# RFID_Shield.net
KiCad netlist of a schematic drawn in EAGLE
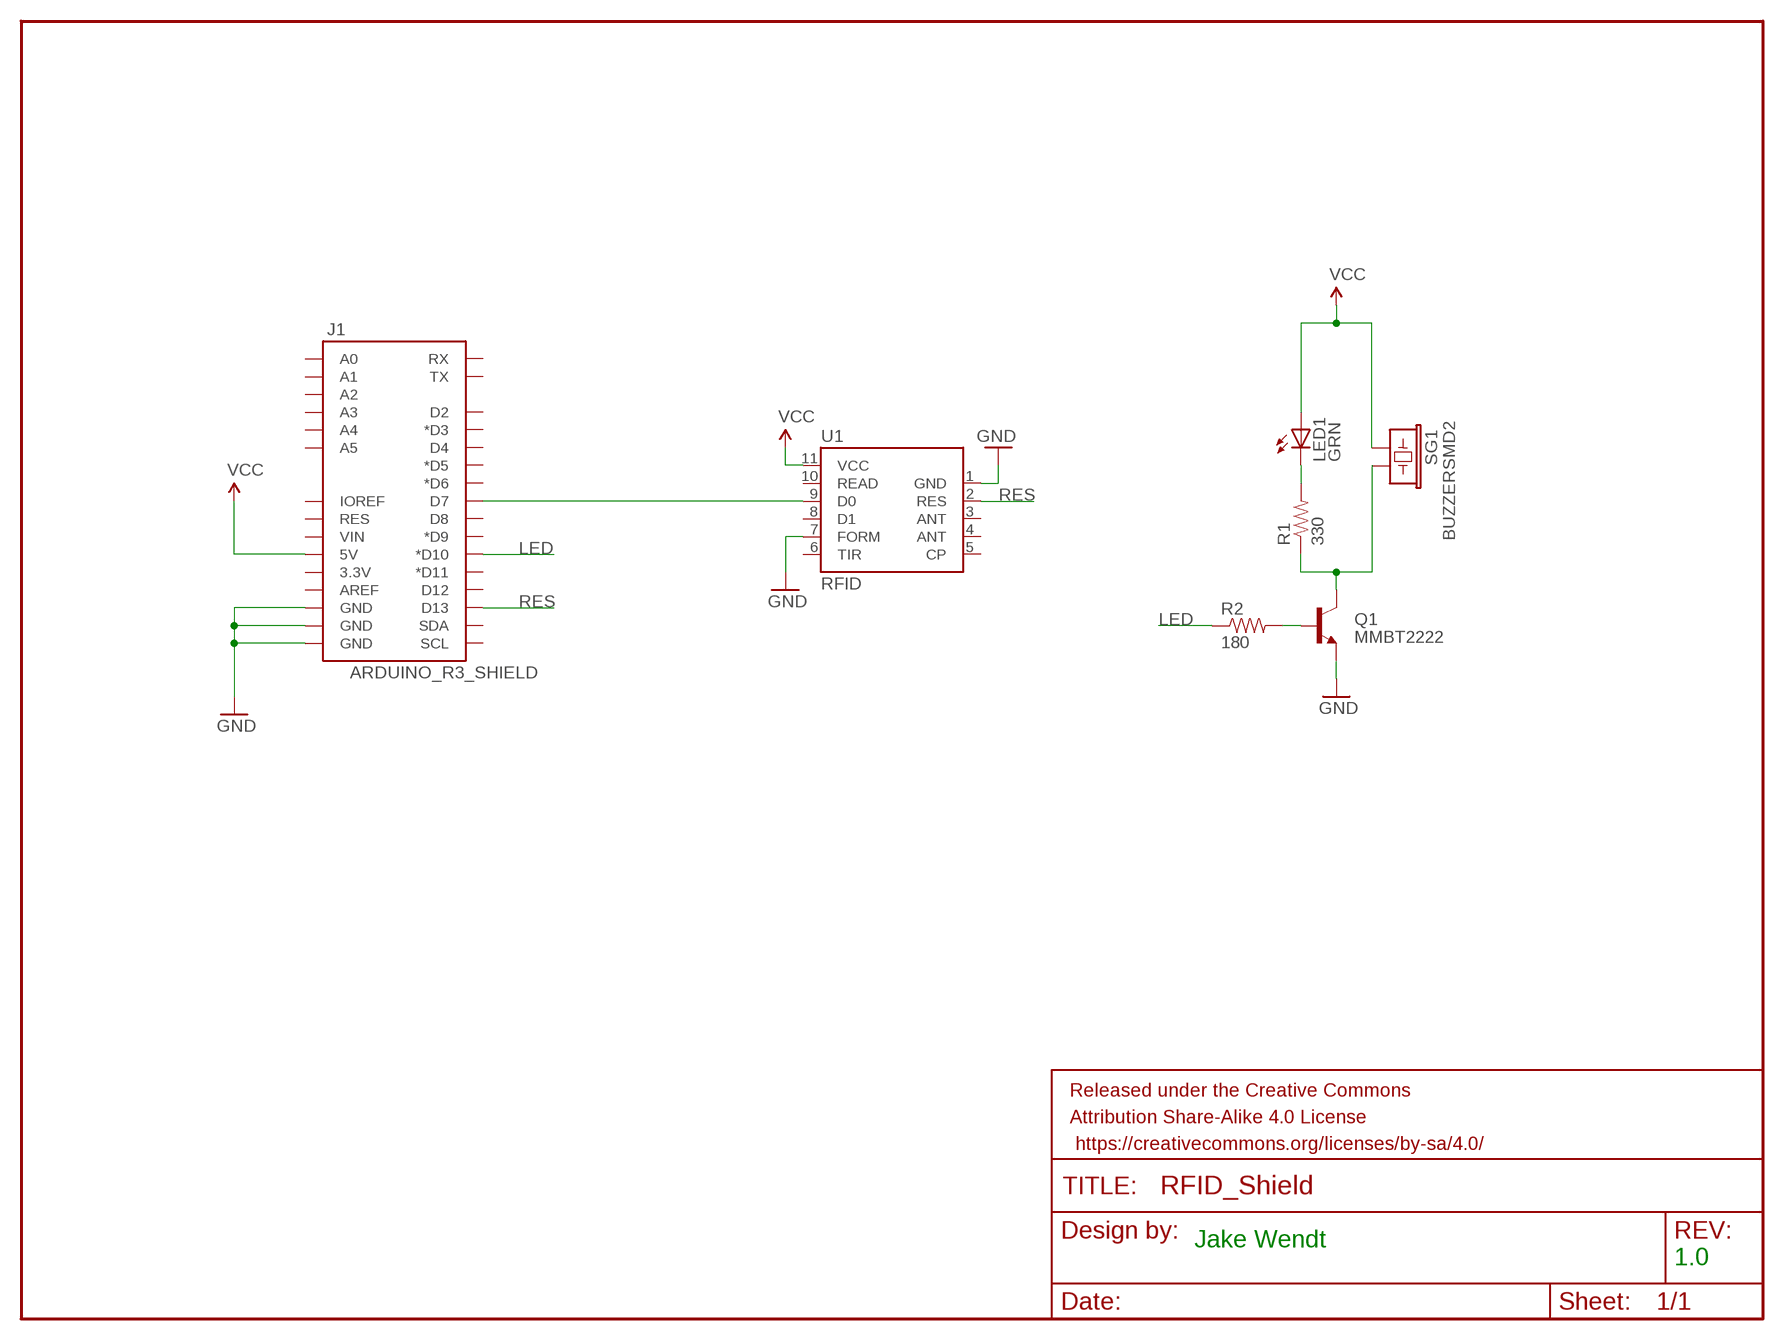
[diagram p0: schematic, sheet 1]

(export (version "E")
  (design (tool "Eeschema 10.0.6"))
  (components
    (comp (ref "FRAME1")
      (value "FRAME-LETTER")
      (footprint "eagle-import:CREATIVE_COMMONS")
      (fields (field (name "DESIGNER") "Jake Wendt"))
      (libsource (lib "eagle-import") (part "FRAME-LETTER"))
    )
    (comp (ref "J1")
      (value "ARDUINO_R3_SHIELD")
      (footprint "eagle-import:UNO_R3_SHIELD")
      (libsource (lib "eagle-import") (part "ARDUINO_R3_SHIELD"))
    )
    (comp (ref "LED1")
      (value "GRN")
      (footprint "eagle-import:LED-0603")
      (libsource (lib "eagle-import") (part "LED0603"))
    )
    (comp (ref "Q1")
      (value "MMBT2222")
      (footprint "eagle-import:SOT23-3")
      (libsource (lib "eagle-import") (part "TRANSISTOR_NPNSOT23-3"))
    )
    (comp (ref "R1")
      (value "330")
      (footprint "eagle-import:0402-RES")
      (libsource (lib "eagle-import") (part "RESISTOR0402-RES"))
    )
    (comp (ref "R2")
      (value "180")
      (footprint "eagle-import:0402-RES")
      (libsource (lib "eagle-import") (part "RESISTOR0402-RES"))
    )
    (comp (ref "SG1")
      (value "BUZZERSMD2")
      (footprint "eagle-import:BUZZER-CCV")
      (libsource (lib "eagle-import") (part "BUZZERSMD2"))
    )
    (comp (ref "U1")
      (value "RFID")
      (footprint "eagle-import:ID_PACKAGE")
      (libsource (lib "eagle-import") (part "RFIDALL"))
    )
  )
  (nets
    (net (code "1") (name "/LED") (class "Default")
      (node (ref "J1") (pin "D10") (pinfunction "*D10_D10") (pintype "bidirectional"))
      (node (ref "R2") (pin "1") (pinfunction "1_1") (pintype "passive"))
    )
    (net (code "2") (name "/RES") (class "Default")
      (node (ref "J1") (pin "D13") (pinfunction "D13_D13") (pintype "bidirectional"))
      (node (ref "U1") (pin "2") (pinfunction "RES_2") (pintype "bidirectional"))
    )
    (net (code "3") (name "GND") (class "Default")
      (node (ref "J1") (pin "GND@0") (pinfunction "GND_GND@0") (pintype "bidirectional"))
      (node (ref "J1") (pin "GND@1") (pinfunction "GND_GND@1") (pintype "bidirectional"))
      (node (ref "J1") (pin "GND@2") (pinfunction "GND_GND@2") (pintype "bidirectional"))
      (node (ref "Q1") (pin "2") (pinfunction "E_2") (pintype "passive"))
      (node (ref "U1") (pin "1") (pinfunction "GND_1") (pintype "bidirectional"))
      (node (ref "U1") (pin "7") (pinfunction "FORM_7") (pintype "bidirectional"))
    )
    (net (code "4") (name "Net-(LED1-PadC)") (class "Default")
      (node (ref "LED1") (pin "C") (pinfunction "C_C") (pintype "passive"))
      (node (ref "R1") (pin "2") (pinfunction "2_2") (pintype "passive"))
    )
    (net (code "5") (name "Net-(Q1-B)") (class "Default")
      (node (ref "Q1") (pin "1") (pinfunction "B_1") (pintype "passive"))
      (node (ref "R2") (pin "2") (pinfunction "2_2") (pintype "passive"))
    )
    (net (code "6") (name "Net-(Q1-C)") (class "Default")
      (node (ref "Q1") (pin "3") (pinfunction "C_3") (pintype "passive"))
      (node (ref "R1") (pin "1") (pinfunction "1_1") (pintype "passive"))
      (node (ref "SG1") (pin "-") (pinfunction "2_-") (pintype "passive"))
    )
    (net (code "7") (name "Net-(U1-D0)") (class "Default")
      (node (ref "J1") (pin "D7") (pinfunction "D7_D7") (pintype "bidirectional"))
      (node (ref "U1") (pin "9") (pinfunction "D0_9") (pintype "bidirectional"))
    )
    (net (code "8") (name "VCC") (class "Default")
      (node (ref "J1") (pin "5V") (pinfunction "5V_5V") (pintype "bidirectional"))
      (node (ref "LED1") (pin "A") (pinfunction "A_A") (pintype "passive"))
      (node (ref "SG1") (pin "+") (pinfunction "1_+") (pintype "passive"))
      (node (ref "U1") (pin "11") (pinfunction "VCC_11") (pintype "bidirectional"))
    )
    (net (code "9") (name "unconnected-(J1-*D3-PadD3)") (class "Default")
      (node (ref "J1") (pin "D3") (pinfunction "*D3_D3") (pintype "bidirectional"))
    )
    (net (code "10") (name "unconnected-(J1-*D5-PadD5)") (class "Default")
      (node (ref "J1") (pin "D5") (pinfunction "*D5_D5") (pintype "bidirectional"))
    )
    (net (code "11") (name "unconnected-(J1-*D6-PadD6)") (class "Default")
      (node (ref "J1") (pin "D6") (pinfunction "*D6_D6") (pintype "bidirectional"))
    )
    (net (code "12") (name "unconnected-(J1-*D9-PadD9)") (class "Default")
      (node (ref "J1") (pin "D9") (pinfunction "*D9_D9") (pintype "bidirectional"))
    )
    (net (code "13") (name "unconnected-(J1-*D11-PadD11)") (class "Default")
      (node (ref "J1") (pin "D11") (pinfunction "*D11_D11") (pintype "bidirectional"))
    )
    (net (code "14") (name "unconnected-(J1-Pad3.3V)") (class "Default")
      (node (ref "J1") (pin "3.3V") (pinfunction "3.3V_3.3V") (pintype "bidirectional"))
    )
    (net (code "15") (name "unconnected-(J1-PadA0)") (class "Default")
      (node (ref "J1") (pin "A0") (pinfunction "A0_A0") (pintype "bidirectional"))
    )
    (net (code "16") (name "unconnected-(J1-PadA1)") (class "Default")
      (node (ref "J1") (pin "A1") (pinfunction "A1_A1") (pintype "bidirectional"))
    )
    (net (code "17") (name "unconnected-(J1-PadA2)") (class "Default")
      (node (ref "J1") (pin "A2") (pinfunction "A2_A2") (pintype "bidirectional"))
    )
    (net (code "18") (name "unconnected-(J1-PadA3)") (class "Default")
      (node (ref "J1") (pin "A3") (pinfunction "A3_A3") (pintype "bidirectional"))
    )
    (net (code "19") (name "unconnected-(J1-PadA4)") (class "Default")
      (node (ref "J1") (pin "A4") (pinfunction "A4_A4") (pintype "bidirectional"))
    )
    (net (code "20") (name "unconnected-(J1-PadA5)") (class "Default")
      (node (ref "J1") (pin "A5") (pinfunction "A5_A5") (pintype "bidirectional"))
    )
    (net (code "21") (name "unconnected-(J1-PadAREF)") (class "Default")
      (node (ref "J1") (pin "AREF") (pinfunction "AREF_AREF") (pintype "bidirectional"))
    )
    (net (code "22") (name "unconnected-(J1-PadD2)") (class "Default")
      (node (ref "J1") (pin "D2") (pinfunction "D2_D2") (pintype "bidirectional"))
    )
    (net (code "23") (name "unconnected-(J1-PadD4)") (class "Default")
      (node (ref "J1") (pin "D4") (pinfunction "D4_D4") (pintype "bidirectional"))
    )
    (net (code "24") (name "unconnected-(J1-PadD8)") (class "Default")
      (node (ref "J1") (pin "D8") (pinfunction "D8_D8") (pintype "bidirectional"))
    )
    (net (code "25") (name "unconnected-(J1-PadD12)") (class "Default")
      (node (ref "J1") (pin "D12") (pinfunction "D12_D12") (pintype "bidirectional"))
    )
    (net (code "26") (name "unconnected-(J1-PadIOREF)") (class "Default")
      (node (ref "J1") (pin "IOREF") (pinfunction "IOREF_IOREF") (pintype "bidirectional"))
    )
    (net (code "27") (name "unconnected-(J1-PadRES)") (class "Default")
      (node (ref "J1") (pin "RES") (pinfunction "RES_RES") (pintype "bidirectional"))
    )
    (net (code "28") (name "unconnected-(J1-PadRX)") (class "Default")
      (node (ref "J1") (pin "RX") (pinfunction "RX_RX") (pintype "bidirectional"))
    )
    (net (code "29") (name "unconnected-(J1-PadSCL)") (class "Default")
      (node (ref "J1") (pin "SCL") (pinfunction "SCL_SCL") (pintype "bidirectional"))
    )
    (net (code "30") (name "unconnected-(J1-PadSDA)") (class "Default")
      (node (ref "J1") (pin "SDA") (pinfunction "SDA_SDA") (pintype "bidirectional"))
    )
    (net (code "31") (name "unconnected-(J1-PadTX)") (class "Default")
      (node (ref "J1") (pin "TX") (pinfunction "TX_TX") (pintype "bidirectional"))
    )
    (net (code "32") (name "unconnected-(J1-PadVIN)") (class "Default")
      (node (ref "J1") (pin "VIN") (pinfunction "VIN_VIN") (pintype "bidirectional"))
    )
    (net (code "33") (name "unconnected-(U1-ANT-Pad3)") (class "Default")
      (node (ref "U1") (pin "3") (pinfunction "ANT_3") (pintype "bidirectional"))
    )
    (net (code "34") (name "unconnected-(U1-ANT-Pad4)") (class "Default")
      (node (ref "U1") (pin "4") (pinfunction "ANT_4") (pintype "bidirectional"))
    )
    (net (code "35") (name "unconnected-(U1-CP-Pad5)") (class "Default")
      (node (ref "U1") (pin "5") (pinfunction "CP_5") (pintype "bidirectional"))
    )
    (net (code "36") (name "unconnected-(U1-D1-Pad8)") (class "Default")
      (node (ref "U1") (pin "8") (pinfunction "D1_8") (pintype "bidirectional"))
    )
    (net (code "37") (name "unconnected-(U1-READ-Pad10)") (class "Default")
      (node (ref "U1") (pin "10") (pinfunction "READ_10") (pintype "bidirectional"))
    )
    (net (code "38") (name "unconnected-(U1-TIR-Pad6)") (class "Default")
      (node (ref "U1") (pin "6") (pinfunction "TIR_6") (pintype "bidirectional"))
    )
  )
)
